# eib-64-nanoz-adapter_OLD.net
KiCad netlist of a schematic drawn in EAGLE
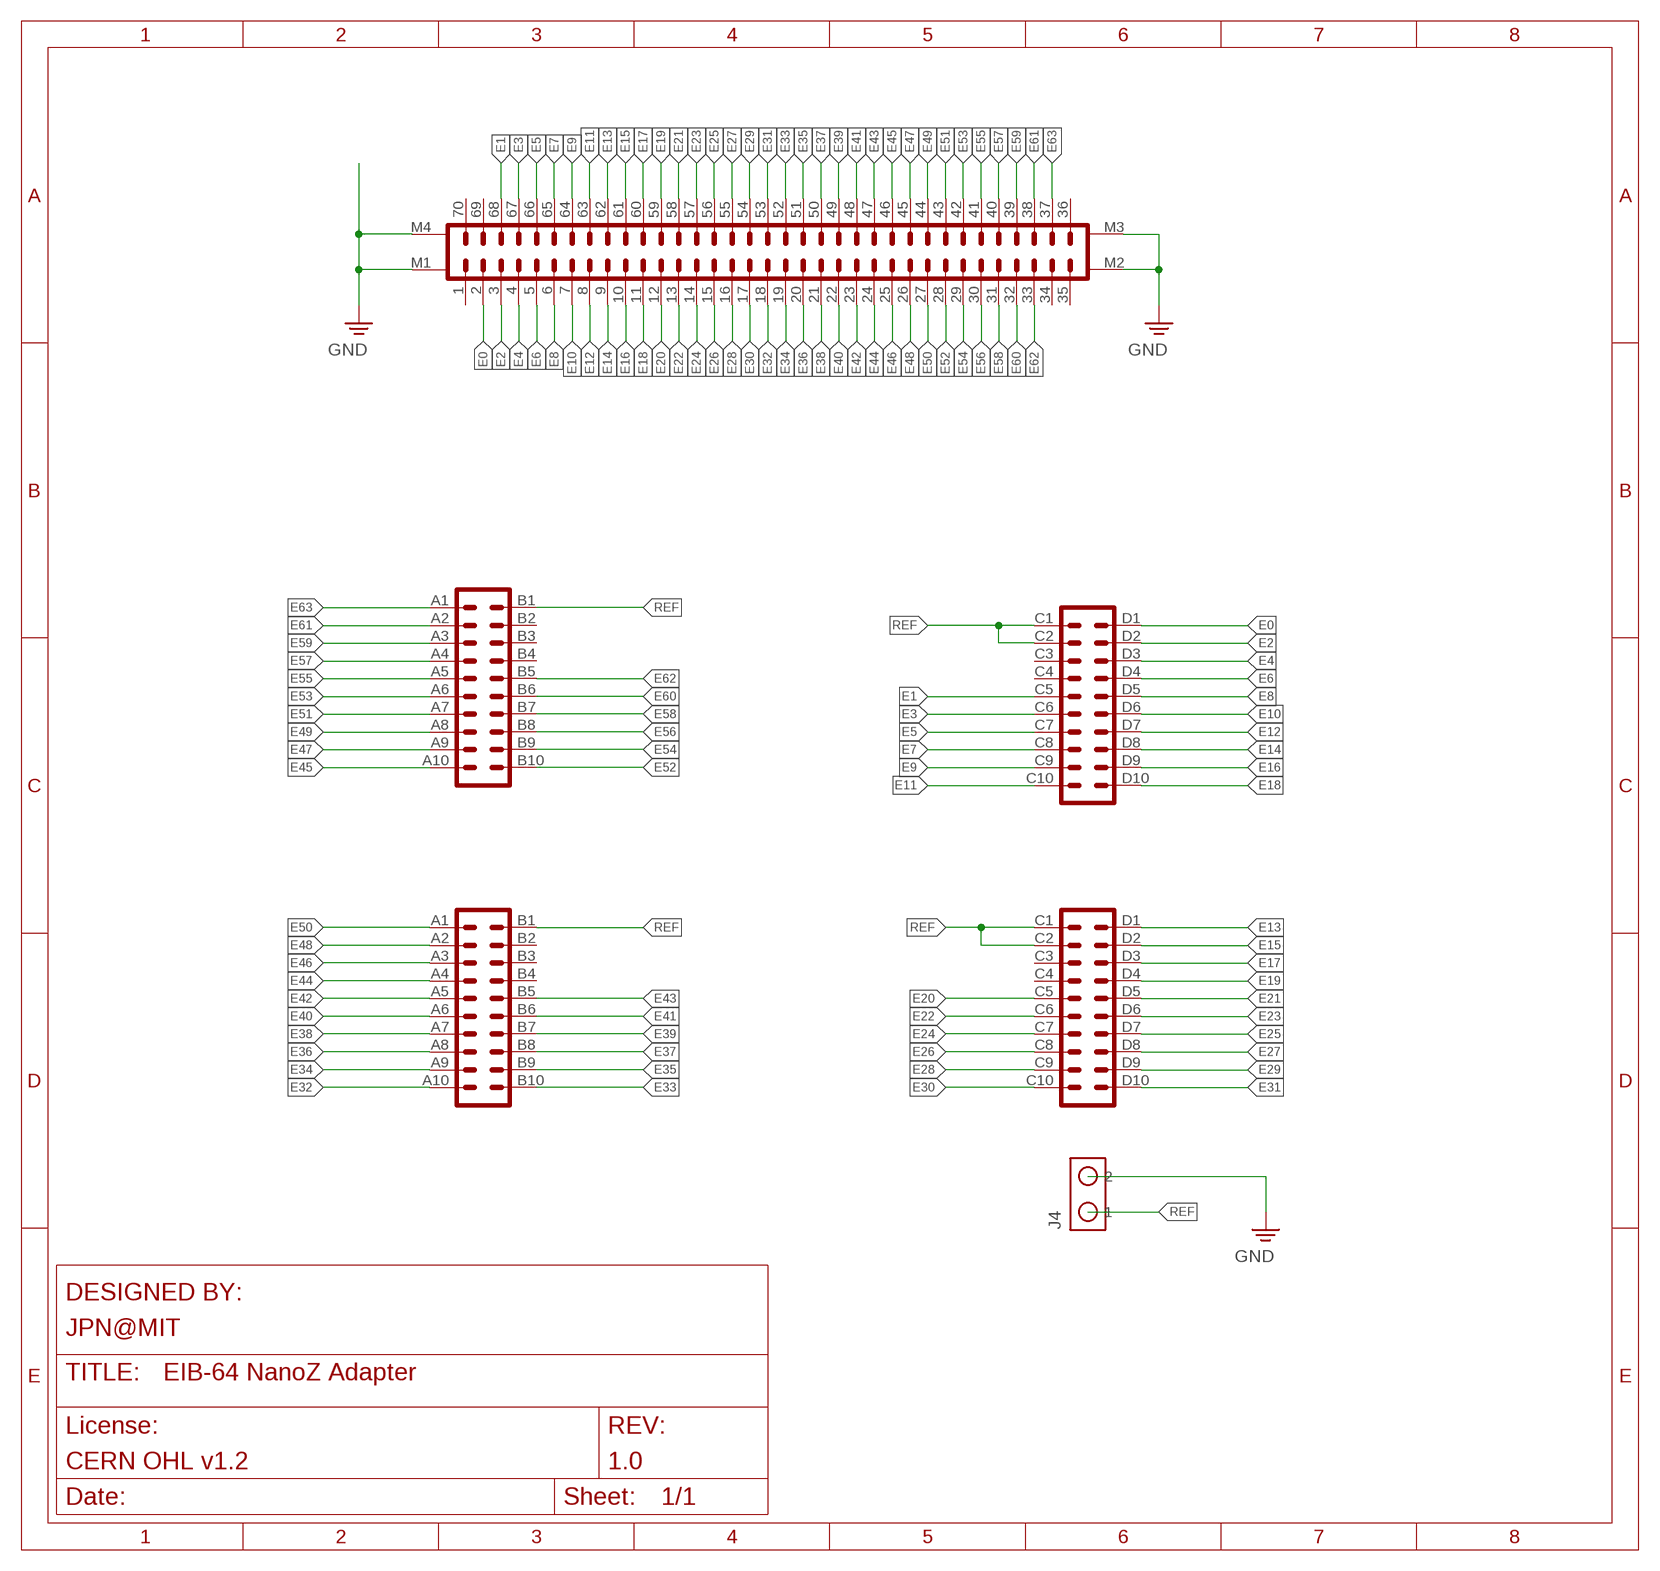
[diagram p0: schematic, sheet 1]

(export (version "E")
  (design (tool "Eeschema 10.0.6"))
  (components
    (comp (ref "J1")
      (value "DF40-REC")
      (footprint "eagle-import:DF40-70HEAD")
      (libsource (lib "eagle-import") (part "PINHD-2X35+4_DF40-70HEAD"))
    )
    (comp (ref "J2")
      (value "PINHD-4X10_MOLC-THRU")
      (footprint "eagle-import:MOLC-110-11-S-Q")
      (libsource (lib "eagle-import") (part "PINHD-4X10_MOLC-THRU"))
    )
    (comp (ref "J3")
      (value "PINHD-4X10_MOLC-THRU")
      (footprint "eagle-import:MOLC-110-11-S-Q")
      (libsource (lib "eagle-import") (part "PINHD-4X10_MOLC-THRU"))
    )
    (comp (ref "J4")
      (value "SCREW2")
      (footprint "eagle-import:SCREW2")
      (libsource (lib "eagle-import") (part "SCREW2"))
    )
  )
  (nets
    (net (code "1") (name "E0") (class "Default")
      (node (ref "J1") (pin "2") (pinfunction "2_2") (pintype "bidirectional"))
      (node (ref "J2") (pin "D1") (pinfunction "20_D1") (pintype "bidirectional"))
    )
    (net (code "2") (name "E1") (class "Default")
      (node (ref "J1") (pin "68") (pinfunction "68_68") (pintype "bidirectional"))
      (node (ref "J2") (pin "C5") (pinfunction "5_C5") (pintype "bidirectional"))
    )
    (net (code "3") (name "E2") (class "Default")
      (node (ref "J1") (pin "3") (pinfunction "3_3") (pintype "bidirectional"))
      (node (ref "J2") (pin "D2") (pinfunction "19_D2") (pintype "bidirectional"))
    )
    (net (code "4") (name "E3") (class "Default")
      (node (ref "J1") (pin "67") (pinfunction "67_67") (pintype "bidirectional"))
      (node (ref "J2") (pin "C6") (pinfunction "6_C6") (pintype "bidirectional"))
    )
    (net (code "5") (name "E4") (class "Default")
      (node (ref "J1") (pin "4") (pinfunction "4_4") (pintype "bidirectional"))
      (node (ref "J2") (pin "D3") (pinfunction "18_D3") (pintype "bidirectional"))
    )
    (net (code "6") (name "E5") (class "Default")
      (node (ref "J1") (pin "66") (pinfunction "66_66") (pintype "bidirectional"))
      (node (ref "J2") (pin "C7") (pinfunction "7_C7") (pintype "bidirectional"))
    )
    (net (code "7") (name "E6") (class "Default")
      (node (ref "J1") (pin "5") (pinfunction "5_5") (pintype "bidirectional"))
      (node (ref "J2") (pin "D4") (pinfunction "17_D4") (pintype "bidirectional"))
    )
    (net (code "8") (name "E7") (class "Default")
      (node (ref "J1") (pin "65") (pinfunction "65_65") (pintype "bidirectional"))
      (node (ref "J2") (pin "C8") (pinfunction "8_C8") (pintype "bidirectional"))
    )
    (net (code "9") (name "E8") (class "Default")
      (node (ref "J1") (pin "6") (pinfunction "6_6") (pintype "bidirectional"))
      (node (ref "J2") (pin "D5") (pinfunction "16_D5") (pintype "bidirectional"))
    )
    (net (code "10") (name "E9") (class "Default")
      (node (ref "J1") (pin "64") (pinfunction "64_64") (pintype "bidirectional"))
      (node (ref "J2") (pin "C9") (pinfunction "9_C9") (pintype "bidirectional"))
    )
    (net (code "11") (name "E10") (class "Default")
      (node (ref "J1") (pin "7") (pinfunction "7_7") (pintype "bidirectional"))
      (node (ref "J2") (pin "D6") (pinfunction "15_D6") (pintype "bidirectional"))
    )
    (net (code "12") (name "E11") (class "Default")
      (node (ref "J1") (pin "63") (pinfunction "63_63") (pintype "bidirectional"))
      (node (ref "J2") (pin "C10") (pinfunction "10_C10") (pintype "bidirectional"))
    )
    (net (code "13") (name "E12") (class "Default")
      (node (ref "J1") (pin "8") (pinfunction "8_8") (pintype "bidirectional"))
      (node (ref "J2") (pin "D7") (pinfunction "14_D7") (pintype "bidirectional"))
    )
    (net (code "14") (name "E13") (class "Default")
      (node (ref "J1") (pin "62") (pinfunction "62_62") (pintype "bidirectional"))
      (node (ref "J3") (pin "D1") (pinfunction "20_D1") (pintype "bidirectional"))
    )
    (net (code "15") (name "E14") (class "Default")
      (node (ref "J1") (pin "9") (pinfunction "9_9") (pintype "bidirectional"))
      (node (ref "J2") (pin "D8") (pinfunction "13_D8") (pintype "bidirectional"))
    )
    (net (code "16") (name "E15") (class "Default")
      (node (ref "J1") (pin "61") (pinfunction "61_61") (pintype "bidirectional"))
      (node (ref "J3") (pin "D2") (pinfunction "19_D2") (pintype "bidirectional"))
    )
    (net (code "17") (name "E16") (class "Default")
      (node (ref "J1") (pin "10") (pinfunction "10_10") (pintype "bidirectional"))
      (node (ref "J2") (pin "D9") (pinfunction "12_D9") (pintype "bidirectional"))
    )
    (net (code "18") (name "E17") (class "Default")
      (node (ref "J1") (pin "60") (pinfunction "60_60") (pintype "bidirectional"))
      (node (ref "J3") (pin "D3") (pinfunction "18_D3") (pintype "bidirectional"))
    )
    (net (code "19") (name "E18") (class "Default")
      (node (ref "J1") (pin "11") (pinfunction "11_11") (pintype "bidirectional"))
      (node (ref "J2") (pin "D10") (pinfunction "11_D10") (pintype "bidirectional"))
    )
    (net (code "20") (name "E19") (class "Default")
      (node (ref "J1") (pin "59") (pinfunction "59_59") (pintype "bidirectional"))
      (node (ref "J3") (pin "D4") (pinfunction "17_D4") (pintype "bidirectional"))
    )
    (net (code "21") (name "E20") (class "Default")
      (node (ref "J1") (pin "12") (pinfunction "12_12") (pintype "bidirectional"))
      (node (ref "J3") (pin "C5") (pinfunction "5_C5") (pintype "bidirectional"))
    )
    (net (code "22") (name "E21") (class "Default")
      (node (ref "J1") (pin "58") (pinfunction "58_58") (pintype "bidirectional"))
      (node (ref "J3") (pin "D5") (pinfunction "16_D5") (pintype "bidirectional"))
    )
    (net (code "23") (name "E22") (class "Default")
      (node (ref "J1") (pin "13") (pinfunction "13_13") (pintype "bidirectional"))
      (node (ref "J3") (pin "C6") (pinfunction "6_C6") (pintype "bidirectional"))
    )
    (net (code "24") (name "E23") (class "Default")
      (node (ref "J1") (pin "57") (pinfunction "57_57") (pintype "bidirectional"))
      (node (ref "J3") (pin "D6") (pinfunction "15_D6") (pintype "bidirectional"))
    )
    (net (code "25") (name "E24") (class "Default")
      (node (ref "J1") (pin "14") (pinfunction "14_14") (pintype "bidirectional"))
      (node (ref "J3") (pin "C7") (pinfunction "7_C7") (pintype "bidirectional"))
    )
    (net (code "26") (name "E25") (class "Default")
      (node (ref "J1") (pin "56") (pinfunction "56_56") (pintype "bidirectional"))
      (node (ref "J3") (pin "D7") (pinfunction "14_D7") (pintype "bidirectional"))
    )
    (net (code "27") (name "E26") (class "Default")
      (node (ref "J1") (pin "15") (pinfunction "15_15") (pintype "bidirectional"))
      (node (ref "J3") (pin "C8") (pinfunction "8_C8") (pintype "bidirectional"))
    )
    (net (code "28") (name "E27") (class "Default")
      (node (ref "J1") (pin "55") (pinfunction "55_55") (pintype "bidirectional"))
      (node (ref "J3") (pin "D8") (pinfunction "13_D8") (pintype "bidirectional"))
    )
    (net (code "29") (name "E28") (class "Default")
      (node (ref "J1") (pin "16") (pinfunction "16_16") (pintype "bidirectional"))
      (node (ref "J3") (pin "C9") (pinfunction "9_C9") (pintype "bidirectional"))
    )
    (net (code "30") (name "E29") (class "Default")
      (node (ref "J1") (pin "54") (pinfunction "54_54") (pintype "bidirectional"))
      (node (ref "J3") (pin "D9") (pinfunction "12_D9") (pintype "bidirectional"))
    )
    (net (code "31") (name "E30") (class "Default")
      (node (ref "J1") (pin "17") (pinfunction "17_17") (pintype "bidirectional"))
      (node (ref "J3") (pin "C10") (pinfunction "10_C10") (pintype "bidirectional"))
    )
    (net (code "32") (name "E31") (class "Default")
      (node (ref "J1") (pin "53") (pinfunction "53_53") (pintype "bidirectional"))
      (node (ref "J3") (pin "D10") (pinfunction "11_D10") (pintype "bidirectional"))
    )
    (net (code "33") (name "E32") (class "Default")
      (node (ref "J1") (pin "18") (pinfunction "18_18") (pintype "bidirectional"))
      (node (ref "J3") (pin "A10") (pinfunction "10_A10") (pintype "bidirectional"))
    )
    (net (code "34") (name "E33") (class "Default")
      (node (ref "J1") (pin "52") (pinfunction "52_52") (pintype "bidirectional"))
      (node (ref "J3") (pin "B10") (pinfunction "11_B10") (pintype "bidirectional"))
    )
    (net (code "35") (name "E34") (class "Default")
      (node (ref "J1") (pin "19") (pinfunction "19_19") (pintype "bidirectional"))
      (node (ref "J3") (pin "A9") (pinfunction "9_A9") (pintype "bidirectional"))
    )
    (net (code "36") (name "E35") (class "Default")
      (node (ref "J1") (pin "51") (pinfunction "51_51") (pintype "bidirectional"))
      (node (ref "J3") (pin "B9") (pinfunction "12_B9") (pintype "bidirectional"))
    )
    (net (code "37") (name "E36") (class "Default")
      (node (ref "J1") (pin "20") (pinfunction "20_20") (pintype "bidirectional"))
      (node (ref "J3") (pin "A8") (pinfunction "8_A8") (pintype "bidirectional"))
    )
    (net (code "38") (name "E37") (class "Default")
      (node (ref "J1") (pin "50") (pinfunction "50_50") (pintype "bidirectional"))
      (node (ref "J3") (pin "B8") (pinfunction "13_B8") (pintype "bidirectional"))
    )
    (net (code "39") (name "E38") (class "Default")
      (node (ref "J1") (pin "21") (pinfunction "21_21") (pintype "bidirectional"))
      (node (ref "J3") (pin "A7") (pinfunction "7_A7") (pintype "bidirectional"))
    )
    (net (code "40") (name "E39") (class "Default")
      (node (ref "J1") (pin "49") (pinfunction "49_49") (pintype "bidirectional"))
      (node (ref "J3") (pin "B7") (pinfunction "14_B7") (pintype "bidirectional"))
    )
    (net (code "41") (name "E40") (class "Default")
      (node (ref "J1") (pin "22") (pinfunction "22_22") (pintype "bidirectional"))
      (node (ref "J3") (pin "A6") (pinfunction "6_A6") (pintype "bidirectional"))
    )
    (net (code "42") (name "E41") (class "Default")
      (node (ref "J1") (pin "48") (pinfunction "48_48") (pintype "bidirectional"))
      (node (ref "J3") (pin "B6") (pinfunction "15_B6") (pintype "bidirectional"))
    )
    (net (code "43") (name "E42") (class "Default")
      (node (ref "J1") (pin "23") (pinfunction "23_23") (pintype "bidirectional"))
      (node (ref "J3") (pin "A5") (pinfunction "5_A5") (pintype "bidirectional"))
    )
    (net (code "44") (name "E43") (class "Default")
      (node (ref "J1") (pin "47") (pinfunction "47_47") (pintype "bidirectional"))
      (node (ref "J3") (pin "B5") (pinfunction "16_B5") (pintype "bidirectional"))
    )
    (net (code "45") (name "E44") (class "Default")
      (node (ref "J1") (pin "24") (pinfunction "24_24") (pintype "bidirectional"))
      (node (ref "J3") (pin "A4") (pinfunction "4_A4") (pintype "bidirectional"))
    )
    (net (code "46") (name "E45") (class "Default")
      (node (ref "J1") (pin "46") (pinfunction "46_46") (pintype "bidirectional"))
      (node (ref "J2") (pin "A10") (pinfunction "10_A10") (pintype "bidirectional"))
    )
    (net (code "47") (name "E46") (class "Default")
      (node (ref "J1") (pin "25") (pinfunction "25_25") (pintype "bidirectional"))
      (node (ref "J3") (pin "A3") (pinfunction "3_A3") (pintype "bidirectional"))
    )
    (net (code "48") (name "E47") (class "Default")
      (node (ref "J1") (pin "45") (pinfunction "45_45") (pintype "bidirectional"))
      (node (ref "J2") (pin "A9") (pinfunction "9_A9") (pintype "bidirectional"))
    )
    (net (code "49") (name "E48") (class "Default")
      (node (ref "J1") (pin "26") (pinfunction "26_26") (pintype "bidirectional"))
      (node (ref "J3") (pin "A2") (pinfunction "2_A2") (pintype "bidirectional"))
    )
    (net (code "50") (name "E49") (class "Default")
      (node (ref "J1") (pin "44") (pinfunction "44_44") (pintype "bidirectional"))
      (node (ref "J2") (pin "A8") (pinfunction "8_A8") (pintype "bidirectional"))
    )
    (net (code "51") (name "E50") (class "Default")
      (node (ref "J1") (pin "27") (pinfunction "27_27") (pintype "bidirectional"))
      (node (ref "J3") (pin "A1") (pinfunction "1_A1") (pintype "bidirectional"))
    )
    (net (code "52") (name "E51") (class "Default")
      (node (ref "J1") (pin "43") (pinfunction "43_43") (pintype "bidirectional"))
      (node (ref "J2") (pin "A7") (pinfunction "7_A7") (pintype "bidirectional"))
    )
    (net (code "53") (name "E52") (class "Default")
      (node (ref "J1") (pin "28") (pinfunction "28_28") (pintype "bidirectional"))
      (node (ref "J2") (pin "B10") (pinfunction "11_B10") (pintype "bidirectional"))
    )
    (net (code "54") (name "E53") (class "Default")
      (node (ref "J1") (pin "42") (pinfunction "42_42") (pintype "bidirectional"))
      (node (ref "J2") (pin "A6") (pinfunction "6_A6") (pintype "bidirectional"))
    )
    (net (code "55") (name "E54") (class "Default")
      (node (ref "J1") (pin "29") (pinfunction "29_29") (pintype "bidirectional"))
      (node (ref "J2") (pin "B9") (pinfunction "12_B9") (pintype "bidirectional"))
    )
    (net (code "56") (name "E55") (class "Default")
      (node (ref "J1") (pin "41") (pinfunction "41_41") (pintype "bidirectional"))
      (node (ref "J2") (pin "A5") (pinfunction "5_A5") (pintype "bidirectional"))
    )
    (net (code "57") (name "E56") (class "Default")
      (node (ref "J1") (pin "30") (pinfunction "30_30") (pintype "bidirectional"))
      (node (ref "J2") (pin "B8") (pinfunction "13_B8") (pintype "bidirectional"))
    )
    (net (code "58") (name "E57") (class "Default")
      (node (ref "J1") (pin "40") (pinfunction "40_40") (pintype "bidirectional"))
      (node (ref "J2") (pin "A4") (pinfunction "4_A4") (pintype "bidirectional"))
    )
    (net (code "59") (name "E58") (class "Default")
      (node (ref "J1") (pin "31") (pinfunction "31_31") (pintype "bidirectional"))
      (node (ref "J2") (pin "B7") (pinfunction "14_B7") (pintype "bidirectional"))
    )
    (net (code "60") (name "E59") (class "Default")
      (node (ref "J1") (pin "39") (pinfunction "39_39") (pintype "bidirectional"))
      (node (ref "J2") (pin "A3") (pinfunction "3_A3") (pintype "bidirectional"))
    )
    (net (code "61") (name "E60") (class "Default")
      (node (ref "J1") (pin "32") (pinfunction "32_32") (pintype "bidirectional"))
      (node (ref "J2") (pin "B6") (pinfunction "15_B6") (pintype "bidirectional"))
    )
    (net (code "62") (name "E61") (class "Default")
      (node (ref "J1") (pin "38") (pinfunction "38_38") (pintype "bidirectional"))
      (node (ref "J2") (pin "A2") (pinfunction "2_A2") (pintype "bidirectional"))
    )
    (net (code "63") (name "E62") (class "Default")
      (node (ref "J1") (pin "33") (pinfunction "33_33") (pintype "bidirectional"))
      (node (ref "J2") (pin "B5") (pinfunction "16_B5") (pintype "bidirectional"))
    )
    (net (code "64") (name "E63") (class "Default")
      (node (ref "J1") (pin "37") (pinfunction "37_37") (pintype "bidirectional"))
      (node (ref "J2") (pin "A1") (pinfunction "1_A1") (pintype "bidirectional"))
    )
    (net (code "65") (name "GND") (class "Default")
      (node (ref "J1") (pin "M1") (pinfunction "M1_M1") (pintype "bidirectional"))
      (node (ref "J1") (pin "M2") (pinfunction "M2_M2") (pintype "bidirectional"))
      (node (ref "J1") (pin "M3") (pinfunction "M3_M3") (pintype "bidirectional"))
      (node (ref "J1") (pin "M4") (pinfunction "M4_M4") (pintype "bidirectional"))
      (node (ref "J4") (pin "P$2") (pinfunction "2_P$2") (pintype "passive"))
    )
    (net (code "66") (name "REF") (class "Default")
      (node (ref "J2") (pin "B1") (pinfunction "20_B1") (pintype "bidirectional"))
      (node (ref "J2") (pin "C1") (pinfunction "1_C1") (pintype "bidirectional"))
      (node (ref "J2") (pin "C2") (pinfunction "2_C2") (pintype "bidirectional"))
      (node (ref "J3") (pin "B1") (pinfunction "20_B1") (pintype "bidirectional"))
      (node (ref "J3") (pin "C1") (pinfunction "1_C1") (pintype "bidirectional"))
      (node (ref "J3") (pin "C2") (pinfunction "2_C2") (pintype "bidirectional"))
      (node (ref "J4") (pin "P$1") (pinfunction "1_P$1") (pintype "passive"))
    )
    (net (code "67") (name "unconnected-(J1-Pad1)") (class "Default")
      (node (ref "J1") (pin "1") (pinfunction "1_1") (pintype "bidirectional"))
    )
    (net (code "68") (name "unconnected-(J1-Pad34)") (class "Default")
      (node (ref "J1") (pin "34") (pinfunction "34_34") (pintype "bidirectional"))
    )
    (net (code "69") (name "unconnected-(J1-Pad35)") (class "Default")
      (node (ref "J1") (pin "35") (pinfunction "35_35") (pintype "bidirectional"))
    )
    (net (code "70") (name "unconnected-(J1-Pad36)") (class "Default")
      (node (ref "J1") (pin "36") (pinfunction "36_36") (pintype "bidirectional"))
    )
    (net (code "71") (name "unconnected-(J1-Pad69)") (class "Default")
      (node (ref "J1") (pin "69") (pinfunction "69_69") (pintype "bidirectional"))
    )
    (net (code "72") (name "unconnected-(J1-Pad70)") (class "Default")
      (node (ref "J1") (pin "70") (pinfunction "70_70") (pintype "bidirectional"))
    )
    (net (code "73") (name "unconnected-(J2A-17-PadB4)") (class "Default")
      (node (ref "J2") (pin "B4") (pinfunction "17_B4") (pintype "bidirectional"))
    )
    (net (code "74") (name "unconnected-(J2A-18-PadB3)") (class "Default")
      (node (ref "J2") (pin "B3") (pinfunction "18_B3") (pintype "bidirectional"))
    )
    (net (code "75") (name "unconnected-(J2A-19-PadB2)") (class "Default")
      (node (ref "J2") (pin "B2") (pinfunction "19_B2") (pintype "bidirectional"))
    )
    (net (code "76") (name "unconnected-(J2B-3-PadC3)") (class "Default")
      (node (ref "J2") (pin "C3") (pinfunction "3_C3") (pintype "bidirectional"))
    )
    (net (code "77") (name "unconnected-(J2B-4-PadC4)") (class "Default")
      (node (ref "J2") (pin "C4") (pinfunction "4_C4") (pintype "bidirectional"))
    )
    (net (code "78") (name "unconnected-(J3A-17-PadB4)") (class "Default")
      (node (ref "J3") (pin "B4") (pinfunction "17_B4") (pintype "bidirectional"))
    )
    (net (code "79") (name "unconnected-(J3A-18-PadB3)") (class "Default")
      (node (ref "J3") (pin "B3") (pinfunction "18_B3") (pintype "bidirectional"))
    )
    (net (code "80") (name "unconnected-(J3A-19-PadB2)") (class "Default")
      (node (ref "J3") (pin "B2") (pinfunction "19_B2") (pintype "bidirectional"))
    )
    (net (code "81") (name "unconnected-(J3B-3-PadC3)") (class "Default")
      (node (ref "J3") (pin "C3") (pinfunction "3_C3") (pintype "bidirectional"))
    )
    (net (code "82") (name "unconnected-(J3B-4-PadC4)") (class "Default")
      (node (ref "J3") (pin "C4") (pinfunction "4_C4") (pintype "bidirectional"))
    )
  )
)
